# Power.net
KiCad netlist of a schematic drawn in Altium Designer
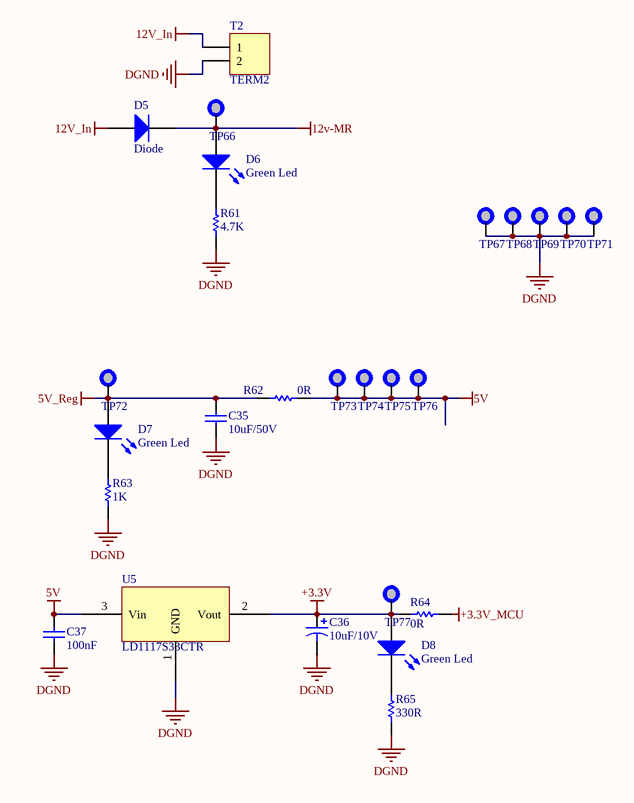
[diagram p0: Power.SchDoc]

(export (version "E")
  (design (tool "Eeschema 10.0.6"))
  (components
    (comp (ref "C35")
      (value "10uF/50V")
      (footprint "1206C")
      (description "Capacitor")
      (fields (field (name "Comment") "CGA5L1X7R1H106K160AC") (field (name "PUBLISHER") "Altium Limited"))
      (libsource (lib "Miscellaneous Devices") (part "Cap"))
    )
    (comp (ref "C36")
      (value "10uF/10V")
      (footprint "TAN-C-C")
      (description "Tantalum")
      (fields (field (name "PUBLISHER") "Altium Limited"))
      (libsource (lib "Miscellaneous Devices") (part "Cap Pol1"))
    )
    (comp (ref "C37")
      (value "100nF")
      (footprint "0603C")
      (description "Capacitor")
      (fields (field (name "Comment") "CGA3E2X7R1H104K080AA") (field (name "PUBLISHER") "Altium Limited"))
      (libsource (lib "Miscellaneous Devices") (part "Cap"))
    )
    (comp (ref "D5")
      (value "Diode")
      (footprint "SMC")
      (description "Default Diode")
      (fields (field (name "PUBLISHER") "Altium Limited"))
      (libsource (lib "Miscellaneous Devices") (part "Diode"))
    )
    (comp (ref "D6")
      (value "Green Led")
      (footprint "0805LED")
      (description "Typical INFRARED GaAs LED")
      (fields (field (name "PUBLISHER") "Altium Limited"))
      (libsource (lib "Miscellaneous Devices") (part "LED0"))
    )
    (comp (ref "D7")
      (value "Green Led")
      (footprint "0805LED")
      (description "Typical INFRARED GaAs LED")
      (fields (field (name "PUBLISHER") "Altium Limited"))
      (libsource (lib "Miscellaneous Devices") (part "LED0"))
    )
    (comp (ref "D8")
      (value "Green Led")
      (footprint "0805LED")
      (description "Typical INFRARED GaAs LED")
      (fields (field (name "PUBLISHER") "Altium Limited"))
      (libsource (lib "Miscellaneous Devices") (part "LED0"))
    )
    (comp (ref "R61")
      (value "4.7K")
      (footprint "1206")
      (description "Resistor")
      (fields (field (name "Comment") "Res1") (field (name "PUBLISHER") "Altium Limited"))
      (libsource (lib "Miscellaneous Devices") (part "Res1"))
    )
    (comp (ref "R62")
      (value "0R")
      (footprint "1206")
      (description "Resistor")
      (fields (field (name "Comment") "Res1") (field (name "PUBLISHER") "Altium Limited"))
      (libsource (lib "Miscellaneous Devices") (part "Res1"))
    )
    (comp (ref "R63")
      (value "1K")
      (footprint "0805")
      (description "Resistor")
      (fields (field (name "Comment") "Res1") (field (name "PUBLISHER") "Altium Limited"))
      (libsource (lib "Miscellaneous Devices") (part "Res1"))
    )
    (comp (ref "R64")
      (value "0R")
      (footprint "1206")
      (description "Resistor")
      (fields (field (name "Comment") "Res1") (field (name "PUBLISHER") "Altium Limited"))
      (libsource (lib "Miscellaneous Devices") (part "Res1"))
    )
    (comp (ref "R65")
      (value "330R")
      (footprint "0805")
      (description "Resistor")
      (fields (field (name "Comment") "Res1") (field (name "PUBLISHER") "Altium Limited"))
      (libsource (lib "Miscellaneous Devices") (part "Res1"))
    )
    (comp (ref "T2")
      (value "TERM2")
      (footprint "term2")
      (description "Header, 2-Pin")
      (fields (field (name "PUBLISHER") "Altium Limited"))
      (libsource (lib "Miscellaneous Connectors") (part "Header 2"))
    )
    (comp (ref "TP66") (value "TestPoint") (footprint "TP") (libsource (lib "SchlibV0.1") (part "TestPoint")))
    (comp (ref "TP67") (value "TestPoint") (footprint "TP") (libsource (lib "SchlibV0.1") (part "TestPoint")))
    (comp (ref "TP68") (value "TestPoint") (footprint "TP") (libsource (lib "SchlibV0.1") (part "TestPoint")))
    (comp (ref "TP69") (value "TestPoint") (footprint "TP") (libsource (lib "SchlibV0.1") (part "TestPoint")))
    (comp (ref "TP70") (value "TestPoint") (footprint "TP") (libsource (lib "SchlibV0.1") (part "TestPoint")))
    (comp (ref "TP71") (value "TestPoint") (footprint "TP") (libsource (lib "SchlibV0.1") (part "TestPoint")))
    (comp (ref "TP72") (value "TestPoint") (footprint "TP") (libsource (lib "SchlibV0.1") (part "TestPoint")))
    (comp (ref "TP73") (value "TestPoint") (footprint "TP") (libsource (lib "SchlibV0.1") (part "TestPoint")))
    (comp (ref "TP74") (value "TestPoint") (footprint "TP") (libsource (lib "SchlibV0.1") (part "TestPoint")))
    (comp (ref "TP75") (value "TestPoint") (footprint "TP") (libsource (lib "SchlibV0.1") (part "TestPoint")))
    (comp (ref "TP76") (value "TestPoint") (footprint "TP") (libsource (lib "SchlibV0.1") (part "TestPoint")))
    (comp (ref "TP77") (value "TestPoint") (footprint "TP") (libsource (lib "SchlibV0.1") (part "TestPoint")))
    (comp (ref "U5")
      (value "LD1117S33CTR")
      (footprint "sot223")
      (libsource (lib "SchlibV0.1") (part "AMS1117"))
    )
  )
  (nets
    (net (code "1") (name "+3.3V") (class "Default")
      (node (ref "C36") (pin "1") (pinfunction "1_1") (pintype "passive"))
      (node (ref "D8") (pin "1") (pinfunction "A_1") (pintype "passive"))
      (node (ref "R64") (pin "1") (pinfunction "1_1") (pintype "passive"))
      (node (ref "TP77") (pin "1") (pintype "passive"))
      (node (ref "U5") (pin "2") (pinfunction "Vout_2") (pintype "passive"))
    )
    (net (code "3") (name "5V") (class "Default")
      (node (ref "C37") (pin "1") (pinfunction "1_1") (pintype "passive"))
      (node (ref "R62") (pin "2") (pinfunction "2_2") (pintype "passive"))
      (node (ref "TP73") (pin "1") (pintype "passive"))
      (node (ref "TP74") (pin "1") (pintype "passive"))
      (node (ref "TP75") (pin "1") (pintype "passive"))
      (node (ref "TP76") (pin "1") (pintype "passive"))
      (node (ref "U5") (pin "3") (pinfunction "Vin_3") (pintype "passive"))
    )
    (net (code "4") (name "5V_Reg") (class "Default")
      (node (ref "C35") (pin "2") (pinfunction "2_2") (pintype "passive"))
      (node (ref "D7") (pin "1") (pinfunction "A_1") (pintype "passive"))
      (node (ref "R62") (pin "1") (pinfunction "1_1") (pintype "passive"))
      (node (ref "TP72") (pin "1") (pintype "passive"))
    )
    (net (code "5") (name "12V_In") (class "Default")
      (node (ref "D5") (pin "1") (pinfunction "A_1") (pintype "passive"))
      (node (ref "T2") (pin "1") (pinfunction "1_1") (pintype "passive"))
    )
    (net (code "6") (name "12v-MR") (class "Default")
      (node (ref "D5") (pin "2") (pinfunction "K_2") (pintype "passive"))
      (node (ref "D6") (pin "1") (pinfunction "A_1") (pintype "passive"))
      (node (ref "TP66") (pin "1") (pintype "passive"))
    )
    (net (code "7") (name "DGND") (class "Default")
      (node (ref "C35") (pin "1") (pinfunction "1_1") (pintype "passive"))
      (node (ref "C36") (pin "2") (pinfunction "2_2") (pintype "passive"))
      (node (ref "C37") (pin "2") (pinfunction "2_2") (pintype "passive"))
      (node (ref "R61") (pin "1") (pinfunction "1_1") (pintype "passive"))
      (node (ref "R63") (pin "1") (pinfunction "1_1") (pintype "passive"))
      (node (ref "R65") (pin "1") (pinfunction "1_1") (pintype "passive"))
      (node (ref "T2") (pin "2") (pinfunction "2_2") (pintype "passive"))
      (node (ref "TP67") (pin "1") (pintype "passive"))
      (node (ref "TP68") (pin "1") (pintype "passive"))
      (node (ref "TP69") (pin "1") (pintype "passive"))
      (node (ref "TP70") (pin "1") (pintype "passive"))
      (node (ref "TP71") (pin "1") (pintype "passive"))
      (node (ref "U5") (pin "1") (pinfunction "GND_1") (pintype "passive"))
    )
    (net (code "8") (name "Net-(D6-K)") (class "Default")
      (node (ref "D6") (pin "2") (pinfunction "K_2") (pintype "passive"))
      (node (ref "R61") (pin "2") (pinfunction "2_2") (pintype "passive"))
    )
    (net (code "9") (name "Net-(D7-K)") (class "Default")
      (node (ref "D7") (pin "2") (pinfunction "K_2") (pintype "passive"))
      (node (ref "R63") (pin "2") (pinfunction "2_2") (pintype "passive"))
    )
    (net (code "10") (name "Net-(D8-K)") (class "Default")
      (node (ref "D8") (pin "2") (pinfunction "K_2") (pintype "passive"))
      (node (ref "R65") (pin "2") (pinfunction "2_2") (pintype "passive"))
    )
    (net (code "11") (name "unconnected-(R64-Pad2)") (class "Default")
      (node (ref "R64") (pin "2") (pinfunction "2_2") (pintype "passive"))
    )
  )
)
